# eeZee_tiny.net
KiCad netlist of a schematic drawn in EAGLE
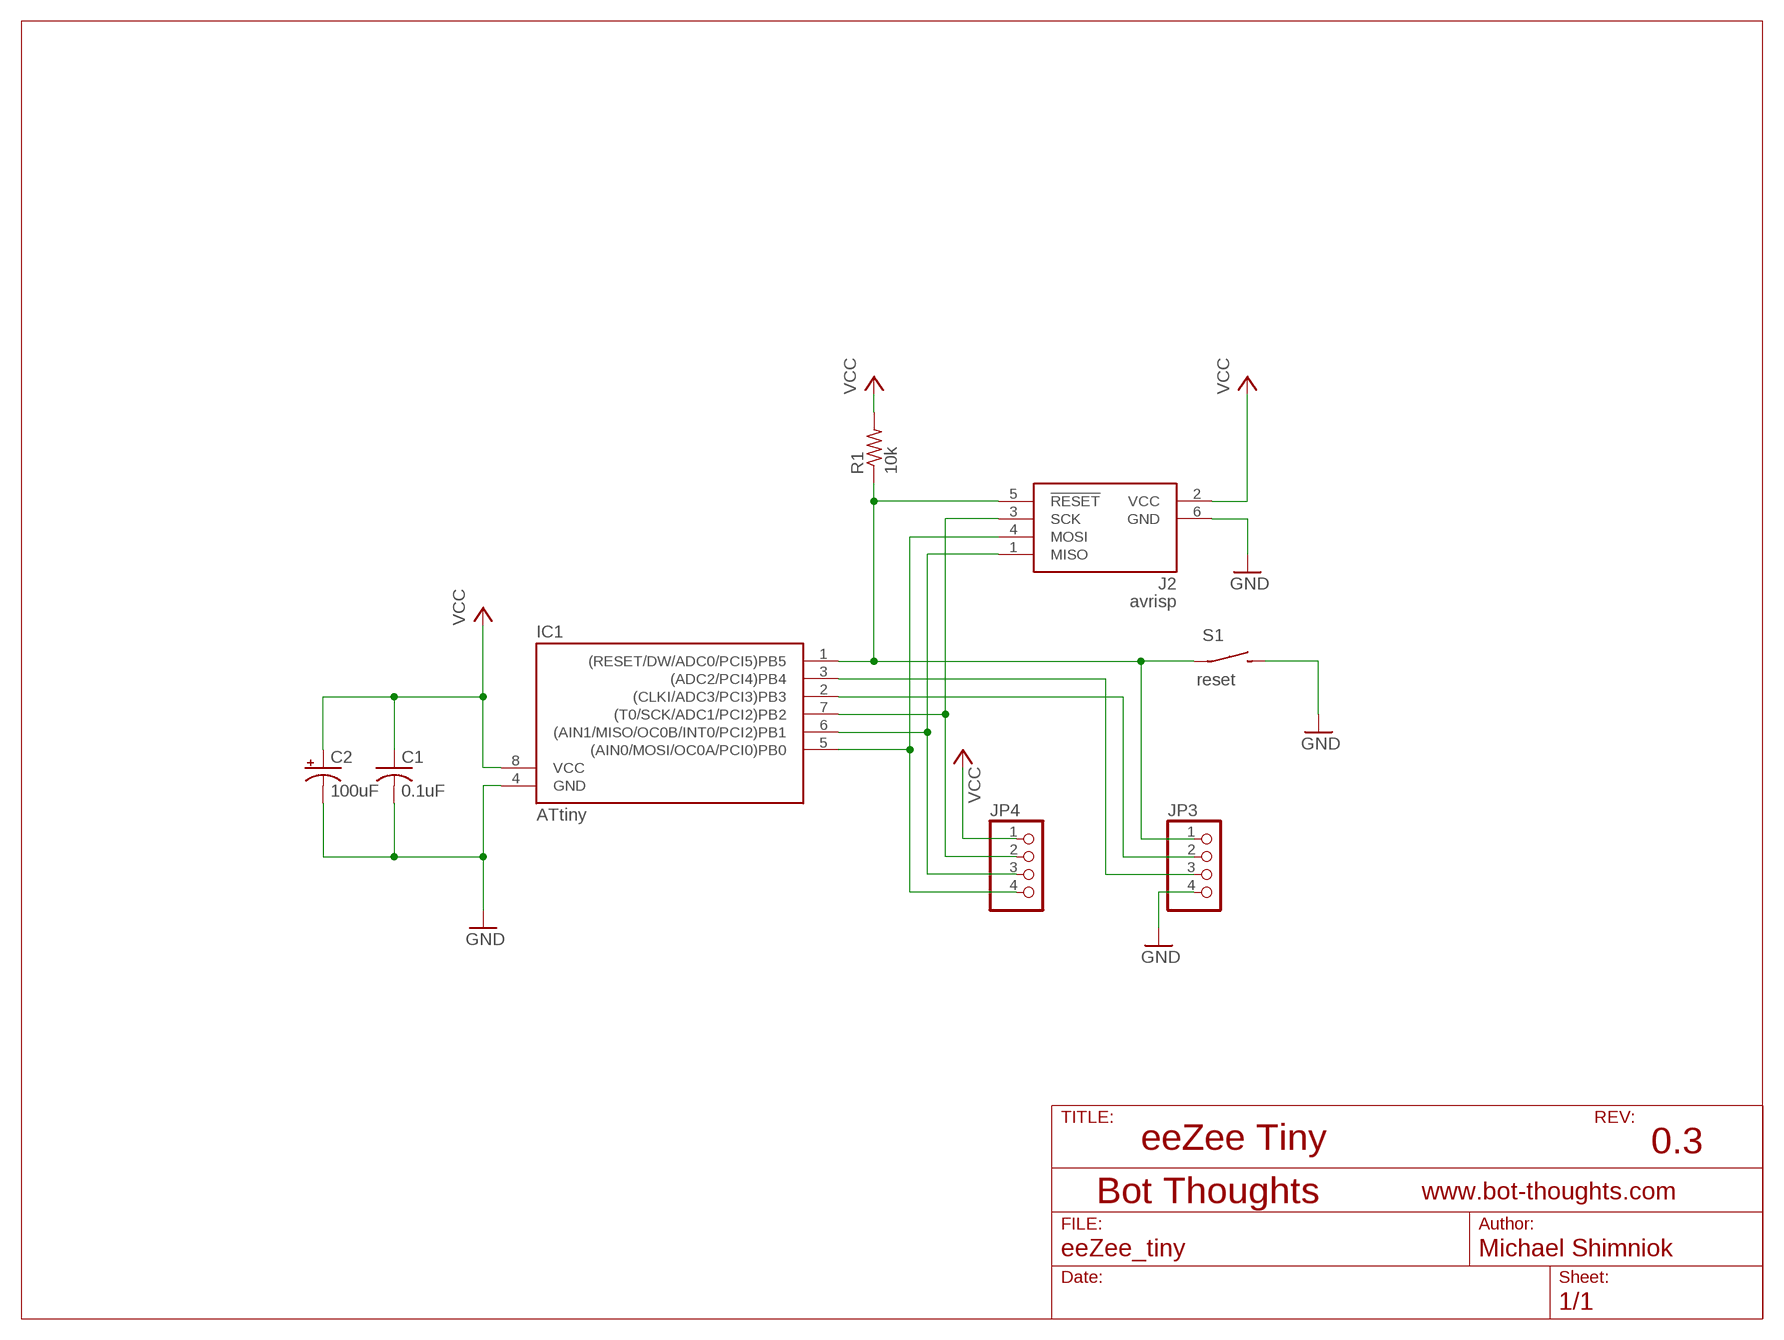
[diagram p0: schematic, sheet 1]

(export (version "E")
  (design (tool "Eeschema 10.0.6"))
  (components
    (comp (ref "C1")
      (value "0.1uF")
      (footprint "eagle-import:C0603")
      (fields (field (name "PARTNO") "0603YC104KAT2A"))
      (libsource (lib "eagle-import") (part "C-USC0603"))
    )
    (comp (ref "C2")
      (value "100uF")
      (footprint "eagle-import:SMC_B")
      (fields (field (name "PARTNO") "F930J107MBA"))
      (libsource (lib "eagle-import") (part "CAP_POL_SMC_B"))
    )
    (comp (ref "IC1")
      (value "ATtiny")
      (footprint "eagle-import:DIL08")
      (fields (field (name "PARTNO") "A08-LC-TT-R"))
      (libsource (lib "eagle-import") (part "ATTINY13P-20"))
    )
    (comp (ref "J2")
      (value "avrisp")
      (footprint "eagle-import:CON6P2R")
      (libsource (lib "eagle-import") (part "AVRISP6"))
    )
    (comp (ref "JP3")
      (value "PINHD-1X04_2.54-S")
      (footprint "eagle-import:1X04-S")
      (libsource (lib "eagle-import") (part "PINHD-1X04_2.54-S"))
    )
    (comp (ref "JP4")
      (value "PINHD-1X04_2.54-S")
      (footprint "eagle-import:1X04-S")
      (libsource (lib "eagle-import") (part "PINHD-1X04_2.54-S"))
    )
    (comp (ref "R1")
      (value "10k")
      (footprint "eagle-import:R0603")
      (fields (field (name "PARTNO") "ERJ-3GEYJ103V"))
      (libsource (lib "eagle-import") (part "R-US_R0603"))
    )
    (comp (ref "S1")
      (value "reset")
      (footprint "eagle-import:6MMTACTILE_RECT")
      (libsource (lib "eagle-import") (part "SPST_TAC_RECT1"))
    )
  )
  (nets
    (net (code "1") (name "GND") (class "Default")
      (node (ref "C1") (pin "2") (pinfunction "2_2") (pintype "passive"))
      (node (ref "C2") (pin "-") (pinfunction "-_-") (pintype "passive"))
      (node (ref "IC1") (pin "4") (pinfunction "GND_4") (pintype "power_in"))
      (node (ref "J2") (pin "6") (pinfunction "GND_6") (pintype "power_in"))
      (node (ref "JP3") (pin "4") (pinfunction "4_4") (pintype "passive"))
      (node (ref "S1") (pin "P$2") (pinfunction "S_P$2") (pintype "passive"))
    )
    (net (code "2") (name "Net-(IC1-(ADC2{slash}PCI4)PB4)") (class "Default")
      (node (ref "IC1") (pin "3") (pinfunction "(ADC2/PCI4)PB4_3") (pintype "bidirectional"))
      (node (ref "JP3") (pin "3") (pinfunction "3_3") (pintype "passive"))
    )
    (net (code "3") (name "Net-(IC1-(AIN0{slash}MOSI{slash}OC0A{slash}PCI0)PB0)") (class "Default")
      (node (ref "IC1") (pin "5") (pinfunction "(AIN0/MOSI/OC0A/PCI0)PB0_5") (pintype "bidirectional"))
      (node (ref "J2") (pin "4") (pinfunction "MOSI_4") (pintype "output"))
      (node (ref "JP4") (pin "4") (pinfunction "4_4") (pintype "passive"))
    )
    (net (code "4") (name "Net-(IC1-(AIN1{slash}MISO{slash}OC0B{slash}INT0{slash}PCI2)PB1)") (class "Default")
      (node (ref "IC1") (pin "6") (pinfunction "(AIN1/MISO/OC0B/INT0/PCI2)PB1_6") (pintype "bidirectional"))
      (node (ref "J2") (pin "1") (pinfunction "MISO_1") (pintype "input"))
      (node (ref "JP4") (pin "3") (pinfunction "3_3") (pintype "passive"))
    )
    (net (code "5") (name "Net-(IC1-(CLKI{slash}ADC3{slash}PCI3)PB3)") (class "Default")
      (node (ref "IC1") (pin "2") (pinfunction "(CLKI/ADC3/PCI3)PB3_2") (pintype "bidirectional"))
      (node (ref "JP3") (pin "2") (pinfunction "2_2") (pintype "passive"))
    )
    (net (code "6") (name "Net-(IC1-(RESET{slash}DW{slash}ADC0{slash}PCI5)PB5)") (class "Default")
      (node (ref "IC1") (pin "1") (pinfunction "(RESET/DW/ADC0/PCI5)PB5_1") (pintype "bidirectional"))
      (node (ref "J2") (pin "5") (pinfunction "~{RESET}_5") (pintype "output"))
      (node (ref "JP3") (pin "1") (pinfunction "1_1") (pintype "passive"))
      (node (ref "R1") (pin "1") (pinfunction "1_1") (pintype "passive"))
      (node (ref "S1") (pin "P$1") (pinfunction "P_P$1") (pintype "passive"))
    )
    (net (code "7") (name "Net-(IC1-(T0{slash}SCK{slash}ADC1{slash}PCI2)PB2)") (class "Default")
      (node (ref "IC1") (pin "7") (pinfunction "(T0/SCK/ADC1/PCI2)PB2_7") (pintype "bidirectional"))
      (node (ref "J2") (pin "3") (pinfunction "SCK_3") (pintype "output"))
      (node (ref "JP4") (pin "2") (pinfunction "2_2") (pintype "passive"))
    )
    (net (code "8") (name "VCC") (class "Default")
      (node (ref "C1") (pin "1") (pinfunction "1_1") (pintype "passive"))
      (node (ref "C2") (pin "+") (pinfunction "+_+") (pintype "passive"))
      (node (ref "IC1") (pin "8") (pinfunction "VCC_8") (pintype "power_in"))
      (node (ref "J2") (pin "2") (pinfunction "VCC_2") (pintype "power_in"))
      (node (ref "JP4") (pin "1") (pinfunction "1_1") (pintype "passive"))
      (node (ref "R1") (pin "2") (pinfunction "2_2") (pintype "passive"))
    )
  )
)
